# Modulator.net
KiCad netlist of a schematic drawn in Altium Designer
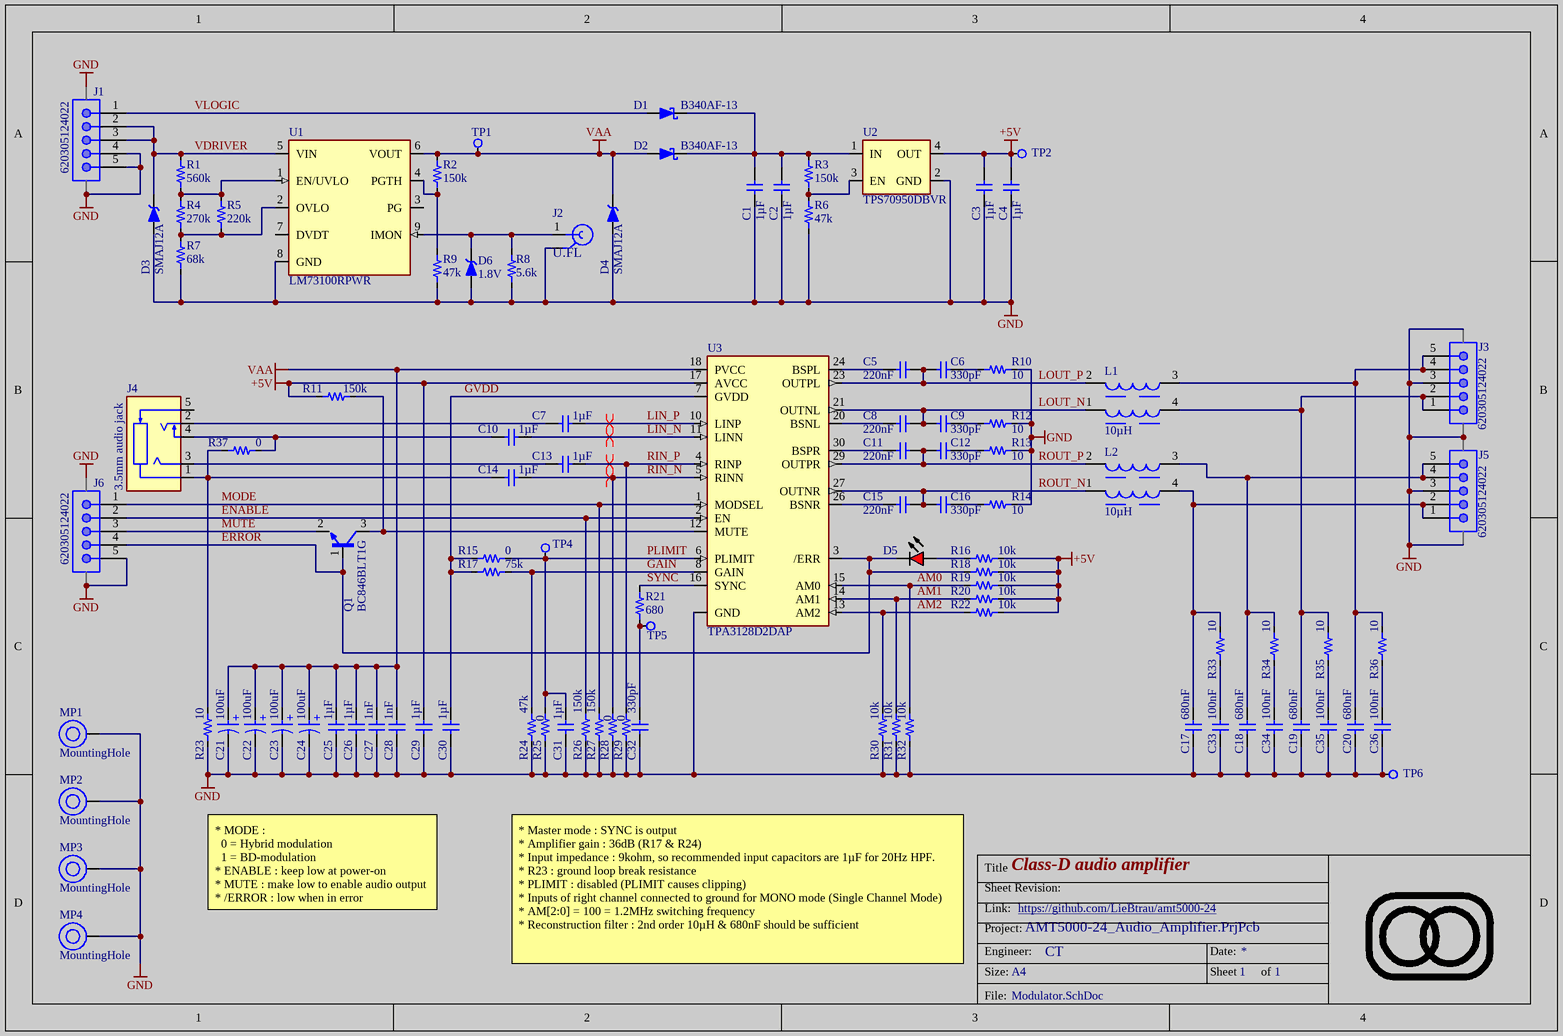
[diagram p0: Modulator.SchDoc]

(export (version "E")
  (design (tool "Eeschema 10.0.6"))
  (components
    (comp (ref "C1")
      (value "1µF")
      (footprint "1206-C-N")
      (description "WCAP-CSGP Multilayer Ceramic Chip Capacitor, General Purpose, size 1206, X7R, 1µF, 50VDC")
      (fields (field (name "TOLERANCE") "10%") (field (name "PAGE PART #") "CCOK105"))
      (libsource (lib "7c7 Engineering") (part "CAP-NP-2"))
    )
    (comp (ref "C2")
      (value "1µF")
      (footprint "1206-C-N")
      (description "WCAP-CSGP Multilayer Ceramic Chip Capacitor, General Purpose, size 1206, X7R, 1µF, 50VDC")
      (fields (field (name "TOLERANCE") "10%") (field (name "PAGE PART #") "CCOK105"))
      (libsource (lib "7c7 Engineering") (part "CAP-NP-2"))
    )
    (comp (ref "C3")
      (value "1µF")
      (footprint "1206-C-N")
      (description "WCAP-CSGP Multilayer Ceramic Chip Capacitor, General Purpose, size 1206, X7R, 1µF, 50VDC")
      (fields (field (name "TOLERANCE") "10%") (field (name "PAGE PART #") "CCOK105"))
      (libsource (lib "7c7 Engineering") (part "CAP-NP-2"))
    )
    (comp (ref "C4")
      (value "1µF")
      (footprint "1206-C-N")
      (description "WCAP-CSGP Multilayer Ceramic Chip Capacitor, General Purpose, size 1206, X7R, 1µF, 50VDC")
      (fields (field (name "TOLERANCE") "10%") (field (name "PAGE PART #") "CCOK105"))
      (libsource (lib "7c7 Engineering") (part "CAP-NP-2"))
    )
    (comp (ref "C5")
      (value "220nF")
      (footprint "0805-C-N")
      (description "WCAP-CSGP Multilayer Ceramic Chip Capacitor, General Purpose, size 0805, X7R, 220nF, 50VDC")
      (fields (field (name "JLCPCB PART #") "C5378") (field (name "TOLERANCE") "10%"))
      (libsource (lib "7c7 Engineering") (part "CAP-NP-2"))
    )
    (comp (ref "C6")
      (value "330pF")
      (footprint "0603-C-N")
      (description "WCAP-CSGP Multilayer Ceramic Chip Capacitor, General Purpose, size 0603, NP0, 330pF, 50VDC")
      (fields (field (name "TOLERANCE") "5%") (field (name "JLCPCB PART #") "C62784"))
      (libsource (lib "7c7 Engineering") (part "CAP-NP-2"))
    )
    (comp (ref "C7")
      (value "1µF")
      (footprint "1206-C-N")
      (description "WCAP-CSGP Multilayer Ceramic Chip Capacitor, General Purpose, size 1206, X7R, 1µF, 50VDC")
      (fields (field (name "TOLERANCE") "10%") (field (name "JLCPCB PART #") "C1848"))
      (libsource (lib "7c7 Engineering") (part "CAP-NP-2"))
    )
    (comp (ref "C8")
      (value "220nF")
      (footprint "0805-C-N")
      (description "WCAP-CSGP Multilayer Ceramic Chip Capacitor, General Purpose, size 0805, X7R, 220nF, 50VDC")
      (fields (field (name "JLCPCB PART #") "C5378") (field (name "TOLERANCE") "10%"))
      (libsource (lib "7c7 Engineering") (part "CAP-NP-2"))
    )
    (comp (ref "C9")
      (value "330pF")
      (footprint "0603-C-N")
      (description "WCAP-CSGP Multilayer Ceramic Chip Capacitor, General Purpose, size 0603, NP0, 330pF, 50VDC")
      (fields (field (name "TOLERANCE") "5%") (field (name "JLCPCB PART #") "C62784"))
      (libsource (lib "7c7 Engineering") (part "CAP-NP-2"))
    )
    (comp (ref "C10")
      (value "1µF")
      (footprint "1206-C-N")
      (description "WCAP-CSGP Multilayer Ceramic Chip Capacitor, General Purpose, size 1206, X7R, 1µF, 50VDC")
      (fields (field (name "TOLERANCE") "10%") (field (name "JLCPCB PART #") "C1848"))
      (libsource (lib "7c7 Engineering") (part "CAP-NP-2"))
    )
    (comp (ref "C11")
      (value "220nF")
      (footprint "0805-C-N")
      (description "WCAP-CSGP Multilayer Ceramic Chip Capacitor, General Purpose, size 0805, X7R, 220nF, 50VDC")
      (fields (field (name "JLCPCB PART #") "C5378") (field (name "TOLERANCE") "10%"))
      (libsource (lib "7c7 Engineering") (part "CAP-NP-2"))
    )
    (comp (ref "C12")
      (value "330pF")
      (footprint "0603-C-N")
      (description "WCAP-CSGP Multilayer Ceramic Chip Capacitor, General Purpose, size 0603, NP0, 330pF, 50VDC")
      (fields (field (name "TOLERANCE") "5%") (field (name "JLCPCB PART #") "C62784"))
      (libsource (lib "7c7 Engineering") (part "CAP-NP-2"))
    )
    (comp (ref "C13")
      (value "1µF")
      (footprint "1206-C-N")
      (description "WCAP-CSGP Multilayer Ceramic Chip Capacitor, General Purpose, size 1206, X7R, 1µF, 50VDC")
      (fields (field (name "TOLERANCE") "10%") (field (name "JLCPCB PART #") "C1848"))
      (libsource (lib "7c7 Engineering") (part "CAP-NP-2"))
    )
    (comp (ref "C14")
      (value "1µF")
      (footprint "1206-C-N")
      (description "WCAP-CSGP Multilayer Ceramic Chip Capacitor, General Purpose, size 1206, X7R, 1µF, 50VDC")
      (fields (field (name "TOLERANCE") "10%") (field (name "JLCPCB PART #") "C1848"))
      (libsource (lib "7c7 Engineering") (part "CAP-NP-2"))
    )
    (comp (ref "C15")
      (value "220nF")
      (footprint "0805-C-N")
      (description "WCAP-CSGP Multilayer Ceramic Chip Capacitor, General Purpose, size 0805, X7R, 220nF, 50VDC")
      (fields (field (name "JLCPCB PART #") "C5378") (field (name "TOLERANCE") "10%"))
      (libsource (lib "7c7 Engineering") (part "CAP-NP-2"))
    )
    (comp (ref "C16")
      (value "330pF")
      (footprint "0603-C-N")
      (description "WCAP-CSGP Multilayer Ceramic Chip Capacitor, General Purpose, size 0603, NP0, 330pF, 50VDC")
      (fields (field (name "TOLERANCE") "5%") (field (name "JLCPCB PART #") "C62784"))
      (libsource (lib "7c7 Engineering") (part "CAP-NP-2"))
    )
    (comp (ref "C17")
      (value "680nF")
      (footprint "1206-C-N")
      (description "WCAP-CSGP Multilayer Ceramic Chip Capacitor, General Purpose, size 1206, X7R, 680nF, 50VDC")
      (fields (field (name "TOLERANCE") "10%") (field (name "JLCPCB PART #") "C282780"))
      (libsource (lib "7c7 Engineering") (part "CAP-NP-2"))
    )
    (comp (ref "C18")
      (value "680nF")
      (footprint "1206-C-N")
      (description "WCAP-CSGP Multilayer Ceramic Chip Capacitor, General Purpose, size 1206, X7R, 680nF, 50VDC")
      (fields (field (name "TOLERANCE") "10%") (field (name "JLCPCB PART #") "C282780"))
      (libsource (lib "7c7 Engineering") (part "CAP-NP-2"))
    )
    (comp (ref "C19")
      (value "680nF")
      (footprint "1206-C-N")
      (description "WCAP-CSGP Multilayer Ceramic Chip Capacitor, General Purpose, size 1206, X7R, 680nF, 50VDC")
      (fields (field (name "TOLERANCE") "10%") (field (name "JLCPCB PART #") "C282780"))
      (libsource (lib "7c7 Engineering") (part "CAP-NP-2"))
    )
    (comp (ref "C20")
      (value "680nF")
      (footprint "1206-C-N")
      (description "WCAP-CSGP Multilayer Ceramic Chip Capacitor, General Purpose, size 1206, X7R, 680nF, 50VDC")
      (fields (field (name "TOLERANCE") "10%") (field (name "JLCPCB PART #") "C282780"))
      (libsource (lib "7c7 Engineering") (part "CAP-NP-2"))
    )
    (comp (ref "C21")
      (value "875585545003")
      (footprint "WCAP-HSAH_D6.3H7.7")
      (description "WCAP-HSAH Aluminum Hybrid Polymer Capacitor, SMT, D6.3 x H7.7mm, 100uF, 25V")
      (fields
        (field (name "JLCPCB PART #") "C22395169")
        (field (name "CAPACITANCE") "100uF")
        (field (name "MANUFACTURER") "Wurth Elektronik")
      )
      (libsource (lib "7c7 Engineering") (part "875585961005"))
    )
    (comp (ref "C22")
      (value "875585545003")
      (footprint "WCAP-HSAH_D6.3H7.7")
      (description "WCAP-HSAH Aluminum Hybrid Polymer Capacitor, SMT, D6.3 x H7.7mm, 100uF, 25V")
      (fields
        (field (name "JLCPCB PART #") "C22395169")
        (field (name "CAPACITANCE") "100uF")
        (field (name "MANUFACTURER") "Wurth Elektronik")
      )
      (libsource (lib "7c7 Engineering") (part "875585961005"))
    )
    (comp (ref "C23")
      (value "875585545003")
      (footprint "WCAP-HSAH_D6.3H7.7")
      (description "WCAP-HSAH Aluminum Hybrid Polymer Capacitor, SMT, D6.3 x H7.7mm, 100uF, 25V")
      (fields
        (field (name "JLCPCB PART #") "C22395169")
        (field (name "CAPACITANCE") "100uF")
        (field (name "MANUFACTURER") "Wurth Elektronik")
      )
      (libsource (lib "7c7 Engineering") (part "875585961005"))
    )
    (comp (ref "C24")
      (value "875585545003")
      (footprint "WCAP-HSAH_D6.3H7.7")
      (description "WCAP-HSAH Aluminum Hybrid Polymer Capacitor, SMT, D6.3 x H7.7mm, 100uF, 25V")
      (fields
        (field (name "JLCPCB PART #") "C22395169")
        (field (name "CAPACITANCE") "100uF")
        (field (name "MANUFACTURER") "Wurth Elektronik")
      )
      (libsource (lib "7c7 Engineering") (part "875585961005"))
    )
    (comp (ref "C25")
      (value "1µF")
      (footprint "1206-C-N")
      (description "WCAP-CSGP Multilayer Ceramic Chip Capacitor, General Purpose, size 1206, X7R, 1µF, 50VDC")
      (fields (field (name "TOLERANCE") "10%") (field (name "JLCPCB PART #") "C1848"))
      (libsource (lib "7c7 Engineering") (part "CAP-NP-2"))
    )
    (comp (ref "C26")
      (value "1µF")
      (footprint "1206-C-N")
      (description "WCAP-CSGP Multilayer Ceramic Chip Capacitor, General Purpose, size 1206, X7R, 1µF, 50VDC")
      (fields (field (name "TOLERANCE") "10%") (field (name "JLCPCB PART #") "C1848"))
      (libsource (lib "7c7 Engineering") (part "CAP-NP-2"))
    )
    (comp (ref "C27")
      (value "1nF")
      (footprint "0603-C-N")
      (description "WCAP-CSGP Multilayer Ceramic Chip Capacitor, General Purpose, size 0603, NP0, 1nF, 100VDC")
      (fields (field (name "JLCPCB PART #") "C153291") (field (name "TOLERANCE") "5%"))
      (libsource (lib "7c7 Engineering") (part "CAP-NP-2"))
    )
    (comp (ref "C28")
      (value "1nF")
      (footprint "0603-C-N")
      (description "WCAP-CSGP Multilayer Ceramic Chip Capacitor, General Purpose, size 0603, NP0, 1nF, 100VDC")
      (fields (field (name "JLCPCB PART #") "C153291") (field (name "TOLERANCE") "5%"))
      (libsource (lib "7c7 Engineering") (part "CAP-NP-2"))
    )
    (comp (ref "C29")
      (value "1µF")
      (footprint "1206-C-N")
      (description "WCAP-CSGP Multilayer Ceramic Chip Capacitor, General Purpose, size 1206, X7R, 1µF, 50VDC")
      (fields (field (name "TOLERANCE") "10%") (field (name "JLCPCB PART #") "C1848"))
      (libsource (lib "7c7 Engineering") (part "CAP-NP-2"))
    )
    (comp (ref "C30")
      (value "1µF")
      (footprint "1206-C-N")
      (description "WCAP-CSGP Multilayer Ceramic Chip Capacitor, General Purpose, size 1206, X7R, 1µF, 50VDC")
      (fields (field (name "TOLERANCE") "10%") (field (name "JLCPCB PART #") "C1848"))
      (libsource (lib "7c7 Engineering") (part "CAP-NP-2"))
    )
    (comp (ref "C31")
      (value "1µF")
      (footprint "1206-C-N")
      (description "WCAP-CSGP Multilayer Ceramic Chip Capacitor, General Purpose, size 1206, X7R, 1µF, 50VDC")
      (fields (field (name "TOLERANCE") "10%") (field (name "JLCPCB PART #") "C1848"))
      (libsource (lib "7c7 Engineering") (part "CAP-NP-2"))
    )
    (comp (ref "C32")
      (value "330pF")
      (footprint "0603-C-N")
      (description "WCAP-CSGP Multilayer Ceramic Chip Capacitor, General Purpose, size 0603, NP0, 330pF, 50VDC")
      (fields (field (name "TOLERANCE") "5%") (field (name "JLCPCB PART #") "C62784"))
      (libsource (lib "7c7 Engineering") (part "CAP-NP-2"))
    )
    (comp (ref "C33")
      (value "100nF")
      (footprint "1206-C-N")
      (description "WCAP-CSGP Multilayer Ceramic Chip Capacitor, General Purpose, size 1206, X7R, 100nF, 50VDC")
      (fields (field (name "JLCPCB PART #") "C82601") (field (name "TOLERANCE") "10%"))
      (libsource (lib "7c7 Engineering") (part "CAP-NP-2"))
    )
    (comp (ref "C34")
      (value "100nF")
      (footprint "1206-C-N")
      (description "WCAP-CSGP Multilayer Ceramic Chip Capacitor, General Purpose, size 1206, X7R, 100nF, 50VDC")
      (fields (field (name "JLCPCB PART #") "C82601") (field (name "TOLERANCE") "10%"))
      (libsource (lib "7c7 Engineering") (part "CAP-NP-2"))
    )
    (comp (ref "C35")
      (value "100nF")
      (footprint "1206-C-N")
      (description "WCAP-CSGP Multilayer Ceramic Chip Capacitor, General Purpose, size 1206, X7R, 100nF, 50VDC")
      (fields (field (name "JLCPCB PART #") "C82601") (field (name "TOLERANCE") "10%"))
      (libsource (lib "7c7 Engineering") (part "CAP-NP-2"))
    )
    (comp (ref "C36")
      (value "100nF")
      (footprint "1206-C-N")
      (description "WCAP-CSGP Multilayer Ceramic Chip Capacitor, General Purpose, size 1206, X7R, 100nF, 50VDC")
      (fields (field (name "JLCPCB PART #") "C82601") (field (name "TOLERANCE") "10%"))
      (libsource (lib "7c7 Engineering") (part "CAP-NP-2"))
    )
    (comp (ref "D1")
      (value "B340AF-13")
      (footprint "DO-214AC_UNI")
      (description "Diode 40 V 3A Surface Mount SMAF")
      (fields (field (name "JLCPCB PART #") "C172880"))
      (libsource (lib "7c7 Engineering") (part "DIODE-SKY-2"))
    )
    (comp (ref "D2")
      (value "B340AF-13")
      (footprint "DO-214AC_UNI")
      (description "Diode 40 V 3A Surface Mount SMAF")
      (fields (field (name "JLCPCB PART #") "C172880"))
      (libsource (lib "7c7 Engineering") (part "DIODE-SKY-2"))
    )
    (comp (ref "D3")
      (value "SMAJ12A")
      (footprint "DO-214AC_UNI")
      (description "SMAJ Series 19.9 V 0.4 kW Surface Mount Uni-Directional TVS Diode - DO-214AC")
      (fields
        (field (name "MANUFACTURER PART NUMBER") "824500121")
        (field (name "MANUFACTURER") "Wurth Elektronik")
      )
      (libsource (lib "7c7 Engineering") (part "DIODE-ZEN-2"))
    )
    (comp (ref "D4")
      (value "SMAJ12A")
      (footprint "DO-214AC_UNI")
      (description "SMAJ Series 19.9 V 0.4 kW Surface Mount Uni-Directional TVS Diode - DO-214AC")
      (fields
        (field (name "MANUFACTURER PART NUMBER") "824500121")
        (field (name "MANUFACTURER") "Wurth Elektronik")
      )
      (libsource (lib "7c7 Engineering") (part "DIODE-ZEN-2"))
    )
    (comp (ref "D5")
      (value "150060RS86000")
      (footprint "WL-SMCW_0603_150060xx8x000")
      (description "WL-SMCW Mono-color Chip LED Waterclear, size 0603, Red, 2V, 60°")
      (fields (field (name "JLCPCB PART #") "C5875741") (field (name "MANUFACTURER") "Wurth Elektronik"))
      (libsource (lib "7c7 Engineering") (part "LED-RED-2"))
    )
    (comp (ref "D6")
      (value "DDZ9678-7")
      (footprint "SOD-123-N")
      (description "Vz=1.8V 1.71V~1.89V Izt=50uA P=500mW")
      (fields
        (field (name "TOLERANCE") "5%")
        (field (name "WORKING VOLTAGE") "1.8V")
        (field (name "JLCPCB PART #") "C150464")
      )
      (libsource (lib "7c7 Engineering") (part "DIODE-ZEN-2"))
    )
    (comp (ref "J1")
      (value "620305124022")
      (footprint "620305124022")
      (description "WR-WTB SMT Male Vertical Shrouded Header, pitch 2mm, 5p")
      (fields (field (name "JLCPCB PART #") "C265085") (field (name "PUBLISHER") "Wurth Elektronik"))
      (libsource (lib "7c7 Engineering") (part "HDR_5P_2MP"))
    )
    (comp (ref "J2")
      (value "U.FL-R-SMT(10)")
      (footprint "HRS-U.FL-R-SMT_V")
      (fields (field (name "JLCPCB PART #") "C88373") (field (name "MANUFACTURER") "Hirose Electric"))
      (libsource (lib "7c7 Engineering") (part "CN_COAX"))
    )
    (comp (ref "J3")
      (value "620305124022")
      (footprint "620305124022")
      (description "WR-WTB SMT Male Vertical Shrouded Header, pitch 2mm, 5p")
      (fields (field (name "JLCPCB PART #") "C265085") (field (name "PUBLISHER") "Wurth Elektronik"))
      (libsource (lib "7c7 Engineering") (part "HDR_5P_2MP"))
    )
    (comp (ref "J4")
      (value "3.5mm audio jack")
      (footprint "SJ2-35863B1-SMT-TR-Footprint-1")
      (description "3.5 mm, Stereo, Right Angle, Surface Mount (SMT), Audio Jack Connector")
      (fields (field (name "JLCPCB PART #") "C381135") (field (name "Comment") "SJ2-35863B1-SMT-TR"))
      (libsource (lib "7c7 Engineering") (part "CN_AUDIO_TRS_2SW"))
    )
    (comp (ref "J5")
      (value "620305124022")
      (footprint "620305124022")
      (description "WR-WTB SMT Male Vertical Shrouded Header, pitch 2mm, 5p")
      (fields (field (name "JLCPCB PART #") "C265085") (field (name "PUBLISHER") "Wurth Elektronik"))
      (libsource (lib "7c7 Engineering") (part "HDR_5P_2MP"))
    )
    (comp (ref "J6")
      (value "620305124022")
      (footprint "620305124022")
      (description "WR-WTB SMT Male Vertical Shrouded Header, pitch 2mm, 5p")
      (fields (field (name "JLCPCB PART #") "C265085") (field (name "PUBLISHER") "Wurth Elektronik"))
      (libsource (lib "7c7 Engineering") (part "HDR_5P_2MP"))
    )
    (comp (ref "L1")
      (value "74434301008100")
      (footprint "WE-LHMD_1008")
      (description "WE-LHMD SMT High Current Inductor, size 1008, 10µH, 3.2A")
      (fields (field (name "MANUFACTURER") "Wurth Elektronik") (field (name "INDUCTANCE") "10µH"))
      (libsource (lib "7c7 Engineering") (part "74434301213220"))
    )
    (comp (ref "L2")
      (value "74434301008100")
      (footprint "WE-LHMD_1008")
      (description "WE-LHMD SMT High Current Inductor, size 1008, 10µH, 3.2A")
      (fields (field (name "MANUFACTURER") "Wurth Elektronik") (field (name "INDUCTANCE") "10µH"))
      (libsource (lib "7c7 Engineering") (part "74434301213220"))
    )
    (comp (ref "MP1")
      (value "MountingHole")
      (footprint "PTH-M3D6.5_VIA-RING")
      (libsource (lib "7c7 Engineering") (part "MECH_NO_BOM"))
    )
    (comp (ref "MP2")
      (value "MountingHole")
      (footprint "PTH-M3D6.5_VIA-RING")
      (libsource (lib "7c7 Engineering") (part "MECH_NO_BOM"))
    )
    (comp (ref "MP3")
      (value "MountingHole")
      (footprint "PTH-M3D6.5_VIA-RING")
      (libsource (lib "7c7 Engineering") (part "MECH_NO_BOM"))
    )
    (comp (ref "MP4")
      (value "MountingHole")
      (footprint "PTH-M3D6.5_VIA-RING")
      (libsource (lib "7c7 Engineering") (part "MECH_NO_BOM"))
    )
    (comp (ref "Q1")
      (value "BC846BLT1G")
      (footprint "SOT-23-3-N")
      (description "NPN Ic=100mA Vceo=65V hfe=200~450 P=225mW SOT-23")
      (fields (field (name "JLCPCB PART #") "C82477"))
      (libsource (lib "7c7 Engineering") (part "BJT-NPN-BEC"))
    )
    (comp (ref "R1")
      (value "560k")
      (footprint "0603-R-N")
      (description "Res Thick Film 0603 560K Ohm 1% 0.1W ±100ppm/°C Molded SMD Punched Carrier T/R")
      (fields (field (name "JLCPCB PART #") "C25822") (field (name "TOLERANCE") "1%"))
      (libsource (lib "7c7 Engineering") (part "RES"))
    )
    (comp (ref "R2")
      (value "150k")
      (footprint "0603-R-N")
      (description "Chip Resistor, Thick Film, General Purpose, 0603, 100mW, 50V, 150 kOhm, +/-1%")
      (fields (field (name "FLIR PART #") "YRES150K-1") (field (name "JLCPCB PART #") "C22807"))
      (libsource (lib "7c7 Engineering") (part "RES"))
    )
    (comp (ref "R3")
      (value "150k")
      (footprint "0603-R-N")
      (description "Chip Resistor, Thick Film, General Purpose, 0603, 100mW, 50V, 150 kOhm, +/-1%")
      (fields (field (name "FLIR PART #") "YRES150K-1") (field (name "JLCPCB PART #") "C22807"))
      (libsource (lib "7c7 Engineering") (part "RES"))
    )
    (comp (ref "R4")
      (value "270k")
      (footprint "0603-R-N")
      (description "SMD Chip Resistor, 270 kOhm, ï¿½ 1%, 100 mW, 0603 [1608 Metric], Thick Film, General Purpose")
      (fields (field (name "JLCPCB PART #") "C22965") (field (name "TOLERANCE") "1%"))
      (libsource (lib "7c7 Engineering") (part "RES"))
    )
    (comp (ref "R5")
      (value "220k")
      (footprint "0603-R-N")
      (description "Res Thick Film 0603 220K Ohm 1% 0.1W(1/10W) ±100ppm/C Pad SMD T/R")
      (fields (field (name "TOLERANCE") "1%") (field (name "FLIR PART #") "YRES220K-1"))
      (libsource (lib "7c7 Engineering") (part "RES"))
    )
    (comp (ref "R6")
      (value "47k")
      (footprint "0603-R-N")
      (description "Chip Resistor, Thick Film, General Purpose, 0603, 100mW, 50V, 47 kOhm, +/-1%")
      (fields (field (name "JLCPCB PART #") "C25819") (field (name "TOLERANCE") "1%"))
      (libsource (lib "7c7 Engineering") (part "RES"))
    )
    (comp (ref "R7")
      (value "68k")
      (footprint "0603-R-N")
      (description "Chip Resistor, Thick Film, General Purpose, 0603, 100mW, 50V, 68 kOhm, +/-1%")
      (fields (field (name "TOLERANCE") "1%") (field (name "JLCPCB PART #") "C114633"))
      (libsource (lib "7c7 Engineering") (part "RES"))
    )
    (comp (ref "R8")
      (value "5.6k")
      (footprint "0603-R-N")
      (description "Res Thick Film 0603 5.6K Ohm 1% 0.1W(1/10W) ±100ppm/C Pad SMD T/R")
      (fields (field (name "JLCPCB PART #") "C23189") (field (name "TOLERANCE") "1%"))
      (libsource (lib "7c7 Engineering") (part "RES"))
    )
    (comp (ref "R9")
      (value "47k")
      (footprint "0603-R-N")
      (description "Chip Resistor, Thick Film, General Purpose, 0603, 100mW, 50V, 47 kOhm, +/-1%")
      (fields (field (name "JLCPCB PART #") "C25819") (field (name "TOLERANCE") "1%"))
      (libsource (lib "7c7 Engineering") (part "RES"))
    )
    (comp (ref "R10")
      (value "10")
      (footprint "1206-R-N")
      (description "Chip Resistor, Thick Film, General Purpose, 1206, 250mW, 200V, 10 Ohm, +/-1%")
      (fields (field (name "JLCPCB PART #") "C17903") (field (name "TOLERANCE") "1%"))
      (libsource (lib "7c7 Engineering") (part "RES"))
    )
    (comp (ref "R11")
      (value "150k")
      (footprint "0603-R-N")
      (description "Chip Resistor, Thick Film, General Purpose, 0603, 100mW, 50V, 150 kOhm, +/-1%")
      (fields (field (name "FLIR PART #") "YRES150K-1") (field (name "JLCPCB PART #") "C22807"))
      (libsource (lib "7c7 Engineering") (part "RES"))
    )
    (comp (ref "R12")
      (value "10")
      (footprint "1206-R-N")
      (description "Chip Resistor, Thick Film, General Purpose, 1206, 250mW, 200V, 10 Ohm, +/-1%")
      (fields (field (name "JLCPCB PART #") "C17903") (field (name "TOLERANCE") "1%"))
      (libsource (lib "7c7 Engineering") (part "RES"))
    )
    (comp (ref "R13")
      (value "10")
      (footprint "1206-R-N")
      (description "Chip Resistor, Thick Film, General Purpose, 1206, 250mW, 200V, 10 Ohm, +/-1%")
      (fields (field (name "JLCPCB PART #") "C17903") (field (name "TOLERANCE") "1%"))
      (libsource (lib "7c7 Engineering") (part "RES"))
    )
    (comp (ref "R14")
      (value "10")
      (footprint "1206-R-N")
      (description "Chip Resistor, Thick Film, General Purpose, 1206, 250mW, 200V, 10 Ohm, +/-1%")
      (fields (field (name "JLCPCB PART #") "C17903") (field (name "TOLERANCE") "1%"))
      (libsource (lib "7c7 Engineering") (part "RES"))
    )
    (comp (ref "R15")
      (value "0")
      (footprint "0603-R-N")
      (description "Chip Jumper, Thick Film, Jumper, 0603, 100mW, 1A, 0 Ohm, <50 mOhm")
      (fields (field (name "FLIR PART #") "YRES0E-1") (field (name "TOLERANCE") "50 mOhm"))
      (libsource (lib "7c7 Engineering") (part "RES"))
    )
    (comp (ref "R16")
      (value "10k")
      (footprint "0603-R-N")
      (description "Chip Resistor, Thick Film, General Purpose, 0603, 100mW, 50V, 10 kOhm, +/-1%")
      (fields (field (name "JLCPCB PART #") "C25804") (field (name "FLIR PART #") "YRES10K-1"))
      (libsource (lib "7c7 Engineering") (part "RES"))
    )
    (comp (ref "R17")
      (value "75k")
      (footprint "0603-R-N")
      (description "Chip Resistor, Thick Film, General Purpose, 0603, 100mW, 50V, 75 kOhm, +/-1%")
      (fields (field (name "JLCPCB PART #") "C23242") (field (name "TOLERANCE") "1%"))
      (libsource (lib "7c7 Engineering") (part "RES"))
    )
    (comp (ref "R18")
      (value "10k")
      (footprint "0603-R-N")
      (description "Chip Resistor, Thick Film, General Purpose, 0603, 100mW, 50V, 10 kOhm, +/-1%")
      (fields (field (name "JLCPCB PART #") "C25804") (field (name "FLIR PART #") "YRES10K-1"))
      (libsource (lib "7c7 Engineering") (part "RES"))
    )
    (comp (ref "R19")
      (value "10k")
      (footprint "0603-R-N")
      (description "Chip Resistor, Thick Film, General Purpose, 0603, 100mW, 50V, 10 kOhm, +/-1%")
      (fields (field (name "JLCPCB PART #") "C25804") (field (name "FLIR PART #") "YRES10K-1"))
      (libsource (lib "7c7 Engineering") (part "RES"))
    )
    (comp (ref "R20")
      (value "10k")
      (footprint "0603-R-N")
      (description "Chip Resistor, Thick Film, General Purpose, 0603, 100mW, 50V, 10 kOhm, +/-1%")
      (fields (field (name "JLCPCB PART #") "C25804") (field (name "FLIR PART #") "YRES10K-1"))
      (libsource (lib "7c7 Engineering") (part "RES"))
    )
    (comp (ref "R21")
      (value "680")
      (footprint "0603-R-N")
      (description "Res Thick Film 0603 680 Ohm 1% 1/10W ±100ppm/°C Molded SMD SMD Paper T/R")
      (fields (field (name "JLCPCB PART #") "C23228") (field (name "TOLERANCE") "1%"))
      (libsource (lib "7c7 Engineering") (part "RES"))
    )
    (comp (ref "R22")
      (value "10k")
      (footprint "0603-R-N")
      (description "Chip Resistor, Thick Film, General Purpose, 0603, 100mW, 50V, 10 kOhm, +/-1%")
      (fields (field (name "JLCPCB PART #") "C25804") (field (name "FLIR PART #") "YRES10K-1"))
      (libsource (lib "7c7 Engineering") (part "RES"))
    )
    (comp (ref "R23")
      (value "10")
      (footprint "0603-R-N")
      (description "Chip Resistor, Thick Film, General Purpose, 0603, 100mW, 50V, 10 Ohm, +/-1%")
      (fields (field (name "TOLERANCE") "1%") (field (name "JLCPCB PART #") "C22859"))
      (libsource (lib "7c7 Engineering") (part "RES"))
    )
    (comp (ref "R24")
      (value "47k")
      (footprint "0603-R-N")
      (description "Chip Resistor, Thick Film, General Purpose, 0603, 100mW, 50V, 47 kOhm, +/-1%")
      (fields (field (name "JLCPCB PART #") "C25819") (field (name "TOLERANCE") "1%"))
      (libsource (lib "7c7 Engineering") (part "RES"))
    )
    (comp (ref "R25")
      (value "0")
      (footprint "0603-R-N")
      (description "Chip Jumper, Thick Film, Jumper, 0603, 100mW, 1A, 0 Ohm, <50 mOhm")
      (fields (field (name "FLIR PART #") "YRES0E-1") (field (name "TOLERANCE") "50 mOhm"))
      (libsource (lib "7c7 Engineering") (part "RES"))
    )
    (comp (ref "R26")
      (value "150k")
      (footprint "0603-R-N")
      (description "Chip Resistor, Thick Film, General Purpose, 0603, 100mW, 50V, 150 kOhm, +/-1%")
      (fields (field (name "FLIR PART #") "YRES150K-1") (field (name "JLCPCB PART #") "C22807"))
      (libsource (lib "7c7 Engineering") (part "RES"))
    )
    (comp (ref "R27")
      (value "150k")
      (footprint "0603-R-N")
      (description "Chip Resistor, Thick Film, General Purpose, 0603, 100mW, 50V, 150 kOhm, +/-1%")
      (fields (field (name "FLIR PART #") "YRES150K-1") (field (name "JLCPCB PART #") "C22807"))
      (libsource (lib "7c7 Engineering") (part "RES"))
    )
    (comp (ref "R28")
      (value "0")
      (footprint "0603-R-N")
      (description "Chip Jumper, Thick Film, Jumper, 0603, 100mW, 1A, 0 Ohm, <50 mOhm")
      (fields (field (name "FLIR PART #") "YRES0E-1") (field (name "TOLERANCE") "50 mOhm"))
      (libsource (lib "7c7 Engineering") (part "RES"))
    )
    (comp (ref "R29")
      (value "0")
      (footprint "0603-R-N")
      (description "Chip Jumper, Thick Film, Jumper, 0603, 100mW, 1A, 0 Ohm, <50 mOhm")
      (fields (field (name "FLIR PART #") "YRES0E-1") (field (name "TOLERANCE") "50 mOhm"))
      (libsource (lib "7c7 Engineering") (part "RES"))
    )
    (comp (ref "R30")
      (value "10k")
      (footprint "0603-R-N")
      (description "Chip Resistor, Thick Film, General Purpose, 0603, 100mW, 50V, 10 kOhm, +/-1%")
      (fields (field (name "JLCPCB PART #") "C25804") (field (name "FLIR PART #") "YRES10K-1"))
      (libsource (lib "7c7 Engineering") (part "RES"))
    )
    (comp (ref "R31")
      (value "10k")
      (footprint "0603-R-N")
      (description "Chip Resistor, Thick Film, General Purpose, 0603, 100mW, 50V, 10 kOhm, +/-1%")
      (fields (field (name "JLCPCB PART #") "C25804") (field (name "FLIR PART #") "YRES10K-1"))
      (libsource (lib "7c7 Engineering") (part "RES"))
    )
    (comp (ref "R32")
      (value "10k")
      (footprint "0603-R-N")
      (description "Chip Resistor, Thick Film, General Purpose, 0603, 100mW, 50V, 10 kOhm, +/-1%")
      (fields (field (name "JLCPCB PART #") "C25804") (field (name "FLIR PART #") "YRES10K-1"))
      (libsource (lib "7c7 Engineering") (part "RES"))
    )
    (comp (ref "R33")
      (value "10")
      (footprint "1206-R-N")
      (description "Chip Resistor, Thick Film, General Purpose, 1206, 250mW, 200V, 10 Ohm, +/-1%")
      (fields (field (name "JLCPCB PART #") "C17903") (field (name "TOLERANCE") "1%"))
      (libsource (lib "7c7 Engineering") (part "RES"))
    )
    (comp (ref "R34")
      (value "10")
      (footprint "1206-R-N")
      (description "Chip Resistor, Thick Film, General Purpose, 1206, 250mW, 200V, 10 Ohm, +/-1%")
      (fields (field (name "JLCPCB PART #") "C17903") (field (name "TOLERANCE") "1%"))
      (libsource (lib "7c7 Engineering") (part "RES"))
    )
    (comp (ref "R35")
      (value "10")
      (footprint "1206-R-N")
      (description "Chip Resistor, Thick Film, General Purpose, 1206, 250mW, 200V, 10 Ohm, +/-1%")
      (fields (field (name "JLCPCB PART #") "C17903") (field (name "TOLERANCE") "1%"))
      (libsource (lib "7c7 Engineering") (part "RES"))
    )
    (comp (ref "R36")
      (value "10")
      (footprint "1206-R-N")
      (description "Chip Resistor, Thick Film, General Purpose, 1206, 250mW, 200V, 10 Ohm, +/-1%")
      (fields (field (name "JLCPCB PART #") "C17903") (field (name "TOLERANCE") "1%"))
      (libsource (lib "7c7 Engineering") (part "RES"))
    )
    (comp (ref "R37")
      (value "0")
      (footprint "0603-R-N")
      (description "Chip Jumper, Thick Film, Jumper, 0603, 100mW, 1A, 0 Ohm, <50 mOhm")
      (fields (field (name "FLIR PART #") "YRES0E-1") (field (name "TOLERANCE") "50 mOhm"))
      (libsource (lib "7c7 Engineering") (part "RES"))
    )
    (comp (ref "TP1")
      (value "Testpad with multiple sizes")
      (footprint "TP_1.5mm_0.3mmHole")
      (description "Testpad land")
      (libsource (lib "7c7 Engineering") (part "Testpad"))
    )
    (comp (ref "TP2")
      (value "Testpad with multiple sizes")
      (footprint "TP_1.5mm_0.3mmHole")
      (description "Testpad land")
      (libsource (lib "7c7 Engineering") (part "Testpad"))
    )
    (comp (ref "TP4")
      (value "Testpad with multiple sizes")
      (footprint "TP_1.5mm_0.3mmHole")
      (description "Testpad land")
      (libsource (lib "7c7 Engineering") (part "Testpad"))
    )
    (comp (ref "TP5")
      (value "Testpad with multiple sizes")
      (footprint "TP_1.5mm_0.3mmHole")
      (description "Testpad land")
      (libsource (lib "7c7 Engineering") (part "Testpad"))
    )
    (comp (ref "TP6")
      (value "Testpad with multiple sizes")
      (footprint "TP_1.5mm_0.3mmHole")
      (description "Testpad land")
      (libsource (lib "7c7 Engineering") (part "Testpad"))
    )
    (comp (ref "U1")
      (value "LM73100RPWR")
      (footprint "VQFN-HR")
      (description "2.7V~23V 5.5A VQFN-10-HR(2x2) Power Distribution Switches ROHS")
      (fields (field (name "JLCPCB PART #") "C3210761"))
      (libsource (lib "7c7 Engineering") (part "IC_LM73100"))
    )
    (comp (ref "U2")
      (value "TPS70950DBVR")
      (footprint "SOT25-N")
      (description "Linear Voltage Regulator IC Positive Fixed 1 Output 5V 150mA SOT-23-5")
      (fields (field (name "JLCPCB PART #") "C96028"))
      (libsource (lib "7c7 Engineering") (part "LDO-with-enable"))
    )
    (comp (ref "U3")
      (value "TPA3128D2DAP")
      (footprint "TSSOP28_PPad")
      (description "Audio Amp Speaker 1-CH Mono/2-CH Stereo 60W Class-D 32-Pin HTSSOP EP Tube")
      (fields (field (name "JLCPCB PART #") "C473362"))
      (libsource (lib "7c7 Engineering") (part "IC_TPA31xx"))
    )
  )
  (nets
    (net (code "1") (name "+5V") (class "Default")
      (node (ref "C29") (pin "2") (pinfunction "2_2") (pintype "passive"))
      (node (ref "C3") (pin "2") (pinfunction "2_2") (pintype "passive"))
      (node (ref "C4") (pin "2") (pinfunction "2_2") (pintype "passive"))
      (node (ref "R11") (pin "1") (pinfunction "1_1") (pintype "passive"))
      (node (ref "R16") (pin "2") (pinfunction "2_2") (pintype "passive"))
      (node (ref "R18") (pin "1") (pinfunction "1_1") (pintype "passive"))
      (node (ref "R19") (pin "1") (pinfunction "1_1") (pintype "passive"))
      (node (ref "R20") (pin "1") (pinfunction "1_1") (pintype "passive"))
      (node (ref "R22") (pin "1") (pinfunction "1_1") (pintype "passive"))
      (node (ref "TP2") (pin "1") (pinfunction "Pad_1") (pintype "passive"))
      (node (ref "U2") (pin "4") (pinfunction "OUT_4") (pintype "power_in"))
      (node (ref "U3") (pin "17") (pinfunction "AVCC_17") (pintype "power_in"))
    )
    (net (code "2") (name "/AM0") (class "Default")
      (node (ref "R19") (pin "2") (pinfunction "2_2") (pintype "passive"))
      (node (ref "R32") (pin "1") (pinfunction "1_1") (pintype "passive"))
      (node (ref "U3") (pin "15") (pinfunction "AM0_15") (pintype "input"))
    )
    (net (code "3") (name "/AM1") (class "Default")
      (node (ref "R20") (pin "2") (pinfunction "2_2") (pintype "passive"))
      (node (ref "R31") (pin "1") (pinfunction "1_1") (pintype "passive"))
      (node (ref "U3") (pin "14") (pinfunction "AM1_14") (pintype "input"))
    )
    (net (code "4") (name "/AM2") (class "Default")
      (node (ref "R22") (pin "2") (pinfunction "2_2") (pintype "passive"))
      (node (ref "R30") (pin "1") (pinfunction "1_1") (pintype "passive"))
      (node (ref "U3") (pin "13") (pinfunction "AM2_13") (pintype "input"))
    )
    (net (code "5") (name "/ENABLE") (class "Default")
      (node (ref "J6") (pin "2") (pinfunction "2_2") (pintype "passive"))
      (node (ref "R26") (pin "2") (pinfunction "2_2") (pintype "passive"))
      (node (ref "U3") (pin "2") (pinfunction "EN_2") (pintype "input"))
    )
    (net (code "6") (name "/ERROR") (class "Default")
      (node (ref "D5") (pin "1") (pinfunction "K_1") (pintype "passive"))
      (node (ref "J6") (pin "4") (pinfunction "4_4") (pintype "passive"))
      (node (ref "Q1") (pin "1") (pinfunction "B_1") (pintype "passive"))
      (node (ref "R18") (pin "2") (pinfunction "2_2") (pintype "passive"))
      (node (ref "U3") (pin "3") (pinfunction "/ERR_3") (pintype "open_collector"))
    )
    (net (code "7") (name "/GAIN") (class "Default")
      (node (ref "R17") (pin "1") (pinfunction "1_1") (pintype "passive"))
      (node (ref "R24") (pin "2") (pinfunction "2_2") (pintype "passive"))
      (node (ref "U3") (pin "8") (pinfunction "GAIN_8") (pintype "passive"))
    )
    (net (code "8") (name "/GVDD") (class "Default")
      (node (ref "C30") (pin "2") (pinfunction "2_2") (pintype "passive"))
      (node (ref "R15") (pin "1") (pinfunction "1_1") (pintype "passive"))
      (node (ref "R17") (pin "2") (pinfunction "2_2") (pintype "passive"))
      (node (ref "U3") (pin "7") (pinfunction "GVDD_7") (pintype "power_in"))
    )
    (net (code "9") (name "/LIN_N") (class "Default")
      (node (ref "C10") (pin "1") (pinfunction "1_1") (pintype "passive"))
      (node (ref "U3") (pin "11") (pinfunction "LINN_11") (pintype "input"))
    )
    (net (code "10") (name "/LIN_P") (class "Default")
      (node (ref "C7") (pin "1") (pinfunction "1_1") (pintype "passive"))
      (node (ref "U3") (pin "10") (pinfunction "LINP_10") (pintype "input"))
    )
    (net (code "11") (name "/LOUT_N") (class "Default")
      (node (ref "C8") (pin "2") (pinfunction "2_2") (pintype "passive"))
      (node (ref "C9") (pin "2") (pinfunction "2_2") (pintype "passive"))
      (node (ref "L1") (pin "1") (pinfunction "1_1") (pintype "passive"))
      (node (ref "U3") (pin "21") (pinfunction "OUTNL_21") (pintype "output"))
    )
    (net (code "12") (name "/LOUT_P") (class "Default")
      (node (ref "C5") (pin "2") (pinfunction "2_2") (pintype "passive"))
      (node (ref "C6") (pin "2") (pinfunction "2_2") (pintype "passive"))
      (node (ref "L1") (pin "2") (pinfunction "2_2") (pintype "passive"))
      (node (ref "U3") (pin "23") (pinfunction "OUTPL_23") (pintype "output"))
    )
    (net (code "13") (name "/MODE") (class "Default")
      (node (ref "J6") (pin "1") (pinfunction "1_1") (pintype "passive"))
      (node (ref "R27") (pin "2") (pinfunction "2_2") (pintype "passive"))
      (node (ref "U3") (pin "1") (pinfunction "MODSEL_1") (pintype "input"))
    )
    (net (code "14") (name "/MUTE") (class "Default")
      (node (ref "J6") (pin "3") (pinfunction "3_3") (pintype "passive"))
      (node (ref "Q1") (pin "2") (pinfunction "E_2") (pintype "passive"))
    )
    (net (code "15") (name "/PLIMIT") (class "Default")
      (node (ref "C31") (pin "2") (pinfunction "2_2") (pintype "passive"))
      (node (ref "R15") (pin "2") (pinfunction "2_2") (pintype "passive"))
      (node (ref "R25") (pin "2") (pinfunction "2_2") (pintype "passive"))
      (node (ref "TP4") (pin "1") (pinfunction "Pad_1") (pintype "passive"))
      (node (ref "U3") (pin "6") (pinfunction "PLIMIT_6") (pintype "input"))
    )
    (net (code "16") (name "/RIN_N") (class "Default")
      (node (ref "C14") (pin "1") (pinfunction "1_1") (pintype "passive"))
      (node (ref "R28") (pin "2") (pinfunction "2_2") (pintype "passive"))
      (node (ref "U3") (pin "5") (pinfunction "RINN_5") (pintype "input"))
    )
    (net (code "17") (name "/RIN_P") (class "Default")
      (node (ref "C13") (pin "1") (pinfunction "1_1") (pintype "passive"))
      (node (ref "R29") (pin "2") (pinfunction "2_2") (pintype "passive"))
      (node (ref "U3") (pin "4") (pinfunction "RINP_4") (pintype "input"))
    )
    (net (code "18") (name "/ROUT_N") (class "Default")
      (node (ref "C15") (pin "2") (pinfunction "2_2") (pintype "passive"))
      (node (ref "C16") (pin "2") (pinfunction "2_2") (pintype "passive"))
      (node (ref "L2") (pin "1") (pinfunction "1_1") (pintype "passive"))
      (node (ref "U3") (pin "27") (pinfunction "OUTNR_27") (pintype "output"))
    )
    (net (code "19") (name "/ROUT_P") (class "Default")
      (node (ref "C11") (pin "2") (pinfunction "2_2") (pintype "passive"))
      (node (ref "C12") (pin "2") (pinfunction "2_2") (pintype "passive"))
      (node (ref "L2") (pin "2") (pinfunction "2_2") (pintype "passive"))
      (node (ref "U3") (pin "29") (pinfunction "OUTPR_29") (pintype "output"))
    )
    (net (code "20") (name "/SYNC") (class "Default")
      (node (ref "R21") (pin "2") (pinfunction "2_2") (pintype "passive"))
      (node (ref "U3") (pin "16") (pinfunction "SYNC_16") (pintype "passive"))
    )
    (net (code "21") (name "/VDRIVER") (class "Default")
      (node (ref "D3") (pin "1") (pinfunction "K_1") (pintype "passive"))
      (node (ref "J1") (pin "2") (pinfunction "2_2") (pintype "passive"))
      (node (ref "J1") (pin "3") (pinfunction "3_3") (pintype "passive"))
      (node (ref "R1") (pin "2") (pinfunction "2_2") (pintype "passive"))
      (node (ref "U1") (pin "5") (pinfunction "VIN_5") (pintype "power_in"))
    )
    (net (code "22") (name "/VLOGIC") (class "Default")
      (node (ref "D1") (pin "2") (pinfunction "A_2") (pintype "passive"))
      (node (ref "J1") (pin "1") (pinfunction "1_1") (pintype "passive"))
    )
    (net (code "23") (name "GND") (class "Default")
      (node (ref "C1") (pin "1") (pinfunction "1_1") (pintype "passive"))
      (node (ref "C17") (pin "1") (pinfunction "1_1") (pintype "passive"))
      (node (ref "C18") (pin "1") (pinfunction "1_1") (pintype "passive"))
      (node (ref "C19") (pin "1") (pinfunction "1_1") (pintype "passive"))
      (node (ref "C2") (pin "1") (pinfunction "1_1") (pintype "passive"))
      (node (ref "C20") (pin "1") (pinfunction "1_1") (pintype "passive"))
      (node (ref "C21") (pin "2") (pinfunction "N_2") (pintype "passive"))
      (node (ref "C22") (pin "2") (pinfunction "N_2") (pintype "passive"))
      (node (ref "C23") (pin "2") (pinfunction "N_2") (pintype "passive"))
      (node (ref "C24") (pin "2") (pinfunction "N_2") (pintype "passive"))
      (node (ref "C25") (pin "2") (pinfunction "2_2") (pintype "passive"))
      (node (ref "C26") (pin "2") (pinfunction "2_2") (pintype "passive"))
      (node (ref "C27") (pin "1") (pinfunction "1_1") (pintype "passive"))
      (node (ref "C28") (pin "1") (pinfunction "1_1") (pintype "passive"))
      (node (ref "C29") (pin "1") (pinfunction "1_1") (pintype "passive"))
      (node (ref "C3") (pin "1") (pinfunction "1_1") (pintype "passive"))
      (node (ref "C30") (pin "1") (pinfunction "1_1") (pintype "passive"))
      (node (ref "C31") (pin "1") (pinfunction "1_1") (pintype "passive"))
      (node (ref "C32") (pin "2") (pinfunction "2_2") (pintype "passive"))
      (node (ref "C33") (pin "1") (pinfunction "1_1") (pintype "passive"))
      (node (ref "C34") (pin "1") (pinfunction "1_1") (pintype "passive"))
      (node (ref "C35") (pin "1") (pinfunction "1_1") (pintype "passive"))
      (node (ref "C36") (pin "1") (pinfunction "1_1") (pintype "passive"))
      (node (ref "C4") (pin "1") (pinfunction "1_1") (pintype "passive"))
      (node (ref "D3") (pin "2") (pinfunction "A_2") (pintype "passive"))
      (node (ref "D4") (pin "2") (pinfunction "A_2") (pintype "passive"))
      (node (ref "D6") (pin "2") (pinfunction "A_2") (pintype "passive"))
      (node (ref "J1") (pin "4") (pinfunction "4_4") (pintype "passive"))
      (node (ref "J1") (pin "5") (pinfunction "5_5") (pintype "passive"))
      (node (ref "J1") (pin "MP1") (pinfunction "MP1_MP1") (pintype "power_in"))
      (node (ref "J1") (pin "MP2") (pinfunction "MP2_MP2") (pintype "power_in"))
      (node (ref "J2") (pin "2") (pinfunction "GND_2") (pintype "passive"))
      (node (ref "J3") (pin "3") (pinfunction "3_3") (pintype "passive"))
      (node (ref "J3") (pin "MP1") (pinfunction "MP1_MP1") (pintype "power_in"))
      (node (ref "J3") (pin "MP2") (pinfunction "MP2_MP2") (pintype "power_in"))
      (node (ref "J5") (pin "3") (pinfunction "3_3") (pintype "passive"))
      (node (ref "J5") (pin "MP1") (pinfunction "MP1_MP1") (pintype "power_in"))
      (node (ref "J5") (pin "MP2") (pinfunction "MP2_MP2") (pintype "power_in"))
      (node (ref "J6") (pin "5") (pinfunction "5_5") (pintype "passive"))
      (node (ref "J6") (pin "MP1") (pinfunction "MP1_MP1") (pintype "power_in"))
      (node (ref "J6") (pin "MP2") (pinfunction "MP2_MP2") (pintype "power_in"))
      (node (ref "MP1") (pin "1") (pinfunction "H1_1") (pintype "passive"))
      (node (ref "MP2") (pin "1") (pinfunction "H1_1") (pintype "passive"))
      (node (ref "MP3") (pin "1") (pinfunction "H1_1") (pintype "passive"))
      (node (ref "MP4") (pin "1") (pinfunction "H1_1") (pintype "passive"))
      (node (ref "R10") (pin "2") (pinfunction "2_2") (pintype "passive"))
      (node (ref "R12") (pin "2") (pinfunction "2_2") (pintype "passive"))
      (node (ref "R13") (pin "2") (pinfunction "2_2") (pintype "passive"))
      (node (ref "R14") (pin "2") (pinfunction "2_2") (pintype "passive"))
      (node (ref "R23") (pin "1") (pinfunction "1_1") (pintype "passive"))
      (node (ref "R24") (pin "1") (pinfunction "1_1") (pintype "passive"))
      (node (ref "R25") (pin "1") (pinfunction "1_1") (pintype "passive"))
      (node (ref "R26") (pin "1") (pinfunction "1_1") (pintype "passive"))
      (node (ref "R27") (pin "1") (pinfunction "1_1") (pintype "passive"))
      (node (ref "R28") (pin "1") (pinfunction "1_1") (pintype "passive"))
      (node (ref "R29") (pin "1") (pinfunction "1_1") (pintype "passive"))
      (node (ref "R30") (pin "2") (pinfunction "2_2") (pintype "passive"))
      (node (ref "R31") (pin "2") (pinfunction "2_2") (pintype "passive"))
      (node (ref "R32") (pin "2") (pinfunction "2_2") (pintype "passive"))
      (node (ref "R6") (pin "2") (pinfunction "2_2") (pintype "passive"))
      (node (ref "R7") (pin "1") (pinfunction "1_1") (pintype "passive"))
      (node (ref "R8") (pin "1") (pinfunction "1_1") (pintype "passive"))
      (node (ref "R9") (pin "1") (pinfunction "1_1") (pintype "passive"))
      (node (ref "TP6") (pin "1") (pinfunction "Pad_1") (pintype "passive"))
      (node (ref "U1") (pin "8") (pinfunction "GND_8") (pintype "power_in"))
      (node (ref "U2") (pin "2") (pinfunction "GND_2") (pintype "power_in"))
      (node (ref "U3") (pin "9") (pinfunction "GND_9") (pintype "passive"))
    )
    (net (code "24") (name "Net-(C6-Pad1)") (class "Default")
      (node (ref "C6") (pin "1") (pinfunction "1_1") (pintype "passive"))
      (node (ref "R10") (pin "1") (pinfunction "1_1") (pintype "passive"))
    )
    (net (code "25") (name "Net-(C7-Pad2)") (class "Default")
      (node (ref "C7") (pin "2") (pinfunction "2_2") (pintype "passive"))
      (node (ref "J4") (pin "2") (pinfunction "2_2") (pintype "passive"))
    )
    (net (code "26") (name "Net-(C9-Pad1)") (class "Default")
      (node (ref "C9") (pin "1") (pinfunction "1_1") (pintype "passive"))
      (node (ref "R12") (pin "1") (pinfunction "1_1") (pintype "passive"))
    )
    (net (code "27") (name "Net-(C10-Pad2)") (class "Default")
      (node (ref "C10") (pin "2") (pinfunction "2_2") (pintype "passive"))
      (node (ref "J4") (pin "4") (pinfunction "4_4") (pintype "passive"))
      (node (ref "R37") (pin "2") (pinfunction "2_2") (pintype "passive"))
    )
    (net (code "28") (name "Net-(C12-Pad1)") (class "Default")
      (node (ref "C12") (pin "1") (pinfunction "1_1") (pintype "passive"))
      (node (ref "R13") (pin "1") (pinfunction "1_1") (pintype "passive"))
    )
    (net (code "29") (name "Net-(C13-Pad2)") (class "Default")
      (node (ref "C13") (pin "2") (pinfunction "2_2") (pintype "passive"))
      (node (ref "J4") (pin "3") (pinfunction "3_3") (pintype "passive"))
    )
    (net (code "30") (name "Net-(C14-Pad2)") (class "Default")
      (node (ref "C14") (pin "2") (pinfunction "2_2") (pintype "passive"))
      (node (ref "J4") (pin "1") (pinfunction "1_1") (pintype "passive"))
      (node (ref "R23") (pin "2") (pinfunction "2_2") (pintype "passive"))
      (node (ref "R37") (pin "1") (pinfunction "1_1") (pintype "passive"))
    )
    (net (code "31") (name "Net-(C16-Pad1)") (class "Default")
      (node (ref "C16") (pin "1") (pinfunction "1_1") (pintype "passive"))
      (node (ref "R14") (pin "1") (pinfunction "1_1") (pintype "passive"))
    )
    (net (code "32") (name "Net-(C17-Pad2)") (class "Default")
      (node (ref "C17") (pin "2") (pinfunction "2_2") (pintype "passive"))
      (node (ref "J5") (pin "1") (pinfunction "1_1") (pintype "passive"))
      (node (ref "J5") (pin "2") (pinfunction "2_2") (pintype "passive"))
      (node (ref "L2") (pin "4") (pinfunction "4_4") (pintype "passive"))
      (node (ref "R33") (pin "2") (pinfunction "2_2") (pintype "passive"))
    )
    (net (code "33") (name "Net-(C18-Pad2)") (class "Default")
      (node (ref "C18") (pin "2") (pinfunction "2_2") (pintype "passive"))
      (node (ref "J5") (pin "4") (pinfunction "4_4") (pintype "passive"))
      (node (ref "J5") (pin "5") (pinfunction "5_5") (pintype "passive"))
      (node (ref "L2") (pin "3") (pinfunction "3_3") (pintype "passive"))
      (node (ref "R34") (pin "2") (pinfunction "2_2") (pintype "passive"))
    )
    (net (code "34") (name "Net-(C19-Pad2)") (class "Default")
      (node (ref "C19") (pin "2") (pinfunction "2_2") (pintype "passive"))
      (node (ref "J3") (pin "1") (pinfunction "1_1") (pintype "passive"))
      (node (ref "J3") (pin "2") (pinfunction "2_2") (pintype "passive"))
      (node (ref "L1") (pin "4") (pinfunction "4_4") (pintype "passive"))
      (node (ref "R35") (pin "2") (pinfunction "2_2") (pintype "passive"))
    )
    (net (code "35") (name "Net-(C20-Pad2)") (class "Default")
      (node (ref "C20") (pin "2") (pinfunction "2_2") (pintype "passive"))
      (node (ref "J3") (pin "4") (pinfunction "4_4") (pintype "passive"))
      (node (ref "J3") (pin "5") (pinfunction "5_5") (pintype "passive"))
      (node (ref "L1") (pin "3") (pinfunction "3_3") (pintype "passive"))
      (node (ref "R36") (pin "2") (pinfunction "2_2") (pintype "passive"))
    )
    (net (code "36") (name "Net-(C32-Pad1)") (class "Default")
      (node (ref "C32") (pin "1") (pinfunction "1_1") (pintype "passive"))
      (node (ref "R21") (pin "1") (pinfunction "1_1") (pintype "passive"))
      (node (ref "TP5") (pin "1") (pinfunction "Pad_1") (pintype "passive"))
    )
    (net (code "37") (name "Net-(C33-Pad2)") (class "Default")
      (node (ref "C33") (pin "2") (pinfunction "2_2") (pintype "passive"))
      (node (ref "R33") (pin "1") (pinfunction "1_1") (pintype "passive"))
    )
    (net (code "38") (name "Net-(C34-Pad2)") (class "Default")
      (node (ref "C34") (pin "2") (pinfunction "2_2") (pintype "passive"))
      (node (ref "R34") (pin "1") (pinfunction "1_1") (pintype "passive"))
    )
    (net (code "39") (name "Net-(C35-Pad2)") (class "Default")
      (node (ref "C35") (pin "2") (pinfunction "2_2") (pintype "passive"))
      (node (ref "R35") (pin "1") (pinfunction "1_1") (pintype "passive"))
    )
    (net (code "40") (name "Net-(C36-Pad2)") (class "Default")
      (node (ref "C36") (pin "2") (pinfunction "2_2") (pintype "passive"))
      (node (ref "R36") (pin "1") (pinfunction "1_1") (pintype "passive"))
    )
    (net (code "41") (name "Net-(D1-K)") (class "Default")
      (node (ref "C1") (pin "2") (pinfunction "2_2") (pintype "passive"))
      (node (ref "C2") (pin "2") (pinfunction "2_2") (pintype "passive"))
      (node (ref "D1") (pin "1") (pinfunction "K_1") (pintype "passive"))
      (node (ref "D2") (pin "1") (pinfunction "K_1") (pintype "passive"))
      (node (ref "R3") (pin "1") (pinfunction "1_1") (pintype "passive"))
      (node (ref "U2") (pin "1") (pinfunction "IN_1") (pintype "power_in"))
    )
    (net (code "42") (name "Net-(D5-A)") (class "Default")
      (node (ref "D5") (pin "2") (pinfunction "A_2") (pintype "passive"))
      (node (ref "R16") (pin "1") (pinfunction "1_1") (pintype "passive"))
    )
    (net (code "43") (name "Net-(D6-K)") (class "Default")
      (node (ref "D6") (pin "1") (pinfunction "K_1") (pintype "passive"))
      (node (ref "J2") (pin "1") (pinfunction "SIG_1") (pintype "passive"))
      (node (ref "R8") (pin "2") (pinfunction "2_2") (pintype "passive"))
      (node (ref "U1") (pin "9") (pinfunction "IMON_9") (pintype "input"))
    )
    (net (code "44") (name "Net-(Q1-C)") (class "Default")
      (node (ref "Q1") (pin "3") (pinfunction "C_3") (pintype "passive"))
      (node (ref "R11") (pin "2") (pinfunction "2_2") (pintype "passive"))
      (node (ref "U3") (pin "12") (pinfunction "MUTE_12") (pintype "passive"))
    )
    (net (code "45") (name "Net-(U1-EN{slash}UVLO)") (class "Default")
      (node (ref "R1") (pin "1") (pinfunction "1_1") (pintype "passive"))
      (node (ref "R4") (pin "2") (pinfunction "2_2") (pintype "passive"))
      (node (ref "R5") (pin "2") (pinfunction "2_2") (pintype "passive"))
      (node (ref "U1") (pin "1") (pinfunction "EN/UVLO_1") (pintype "input"))
    )
    (net (code "46") (name "Net-(U1-OVLO)") (class "Default")
      (node (ref "R4") (pin "1") (pinfunction "1_1") (pintype "passive"))
      (node (ref "R5") (pin "1") (pinfunction "1_1") (pintype "passive"))
      (node (ref "R7") (pin "2") (pinfunction "2_2") (pintype "passive"))
      (node (ref "U1") (pin "2") (pinfunction "OVLO_2") (pintype "passive"))
    )
    (net (code "47") (name "Net-(U1-PGTH)") (class "Default")
      (node (ref "R2") (pin "2") (pinfunction "2_2") (pintype "passive"))
      (node (ref "R9") (pin "2") (pinfunction "2_2") (pintype "passive"))
      (node (ref "U1") (pin "4") (pinfunction "PGTH_4") (pintype "passive"))
    )
    (net (code "48") (name "Net-(U2-EN)") (class "Default")
      (node (ref "R3") (pin "2") (pinfunction "2_2") (pintype "passive"))
      (node (ref "R6") (pin "1") (pinfunction "1_1") (pintype "passive"))
      (node (ref "U2") (pin "3") (pinfunction "EN_3") (pintype "passive"))
    )
    (net (code "49") (name "Net-(U3-BSNL)") (class "Default")
      (node (ref "C8") (pin "1") (pinfunction "1_1") (pintype "passive"))
      (node (ref "U3") (pin "20") (pinfunction "BSNL_20") (pintype "passive"))
    )
    (net (code "50") (name "Net-(U3-BSNR)") (class "Default")
      (node (ref "C15") (pin "1") (pinfunction "1_1") (pintype "passive"))
      (node (ref "U3") (pin "26") (pinfunction "BSNR_26") (pintype "passive"))
    )
    (net (code "51") (name "Net-(U3-BSPL)") (class "Default")
      (node (ref "C5") (pin "1") (pinfunction "1_1") (pintype "passive"))
      (node (ref "U3") (pin "24") (pinfunction "BSPL_24") (pintype "passive"))
    )
    (net (code "52") (name "Net-(U3-BSPR)") (class "Default")
      (node (ref "C11") (pin "1") (pinfunction "1_1") (pintype "passive"))
      (node (ref "U3") (pin "30") (pinfunction "BSPR_30") (pintype "passive"))
    )
    (net (code "53") (name "VAA") (class "Default")
      (node (ref "C21") (pin "1") (pinfunction "P_1") (pintype "passive"))
      (node (ref "C22") (pin "1") (pinfunction "P_1") (pintype "passive"))
      (node (ref "C23") (pin "1") (pinfunction "P_1") (pintype "passive"))
      (node (ref "C24") (pin "1") (pinfunction "P_1") (pintype "passive"))
      (node (ref "C25") (pin "1") (pinfunction "1_1") (pintype "passive"))
      (node (ref "C26") (pin "1") (pinfunction "1_1") (pintype "passive"))
      (node (ref "C27") (pin "2") (pinfunction "2_2") (pintype "passive"))
      (node (ref "C28") (pin "2") (pinfunction "2_2") (pintype "passive"))
      (node (ref "D2") (pin "2") (pinfunction "A_2") (pintype "passive"))
      (node (ref "D4") (pin "1") (pinfunction "K_1") (pintype "passive"))
      (node (ref "R2") (pin "1") (pinfunction "1_1") (pintype "passive"))
      (node (ref "TP1") (pin "1") (pinfunction "Pad_1") (pintype "passive"))
      (node (ref "U1") (pin "6") (pinfunction "VOUT_6") (pintype "passive"))
      (node (ref "U3") (pin "18") (pinfunction "PVCC_18") (pintype "passive"))
    )
    (net (code "54") (name "unconnected-(J4-Pad5)") (class "Default")
      (node (ref "J4") (pin "5") (pinfunction "5_5") (pintype "passive"))
    )
    (net (code "55") (name "unconnected-(U1-DVDT-Pad7)") (class "Default")
      (node (ref "U1") (pin "7") (pinfunction "DVDT_7") (pintype "passive"))
    )
    (net (code "56") (name "unconnected-(U1-PG-Pad3)") (class "Default")
      (node (ref "U1") (pin "3") (pinfunction "PG_3") (pintype "open_collector"))
    )
  )
)
